# Sensor-platiene.net
KiCad netlist of a schematic drawn in EAGLE
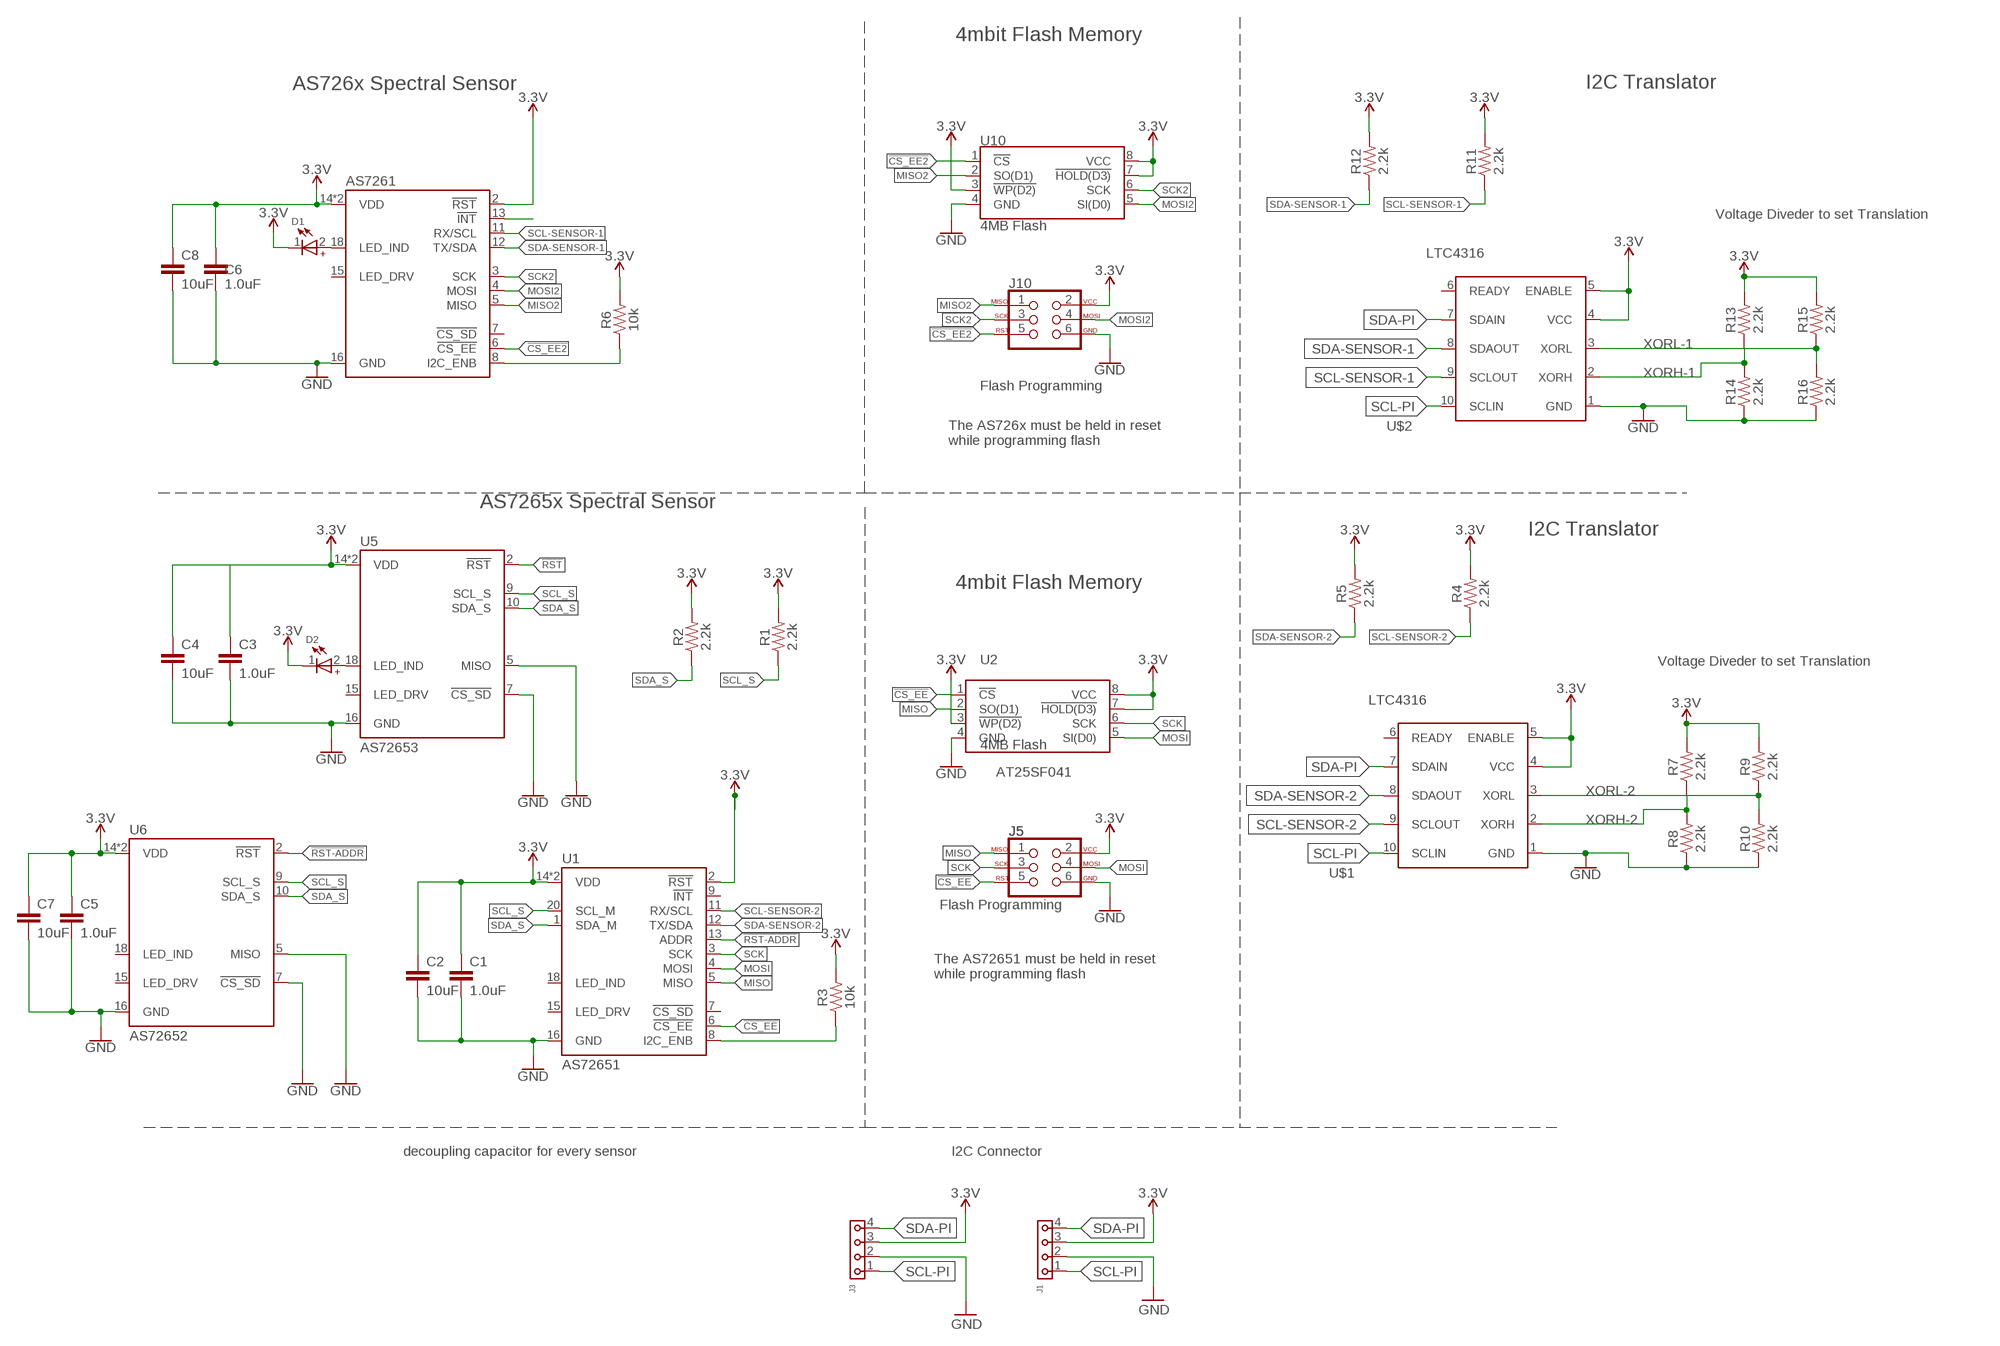
[diagram p0: schematic, sheet 1]

(export (version "E")
  (design (tool "Eeschema 10.0.6"))
  (components
    (comp (ref "AS7261")
      (value "IR")
      (footprint "eagle-import:LGA20")
      (libsource (lib "eagle-import") (part "AS726XIR"))
    )
    (comp (ref "C1")
      (value "1.0uF")
      (footprint "eagle-import:0603")
      (libsource (lib "eagle-import") (part "1.0UF-0603-16V-10%"))
    )
    (comp (ref "C2")
      (value "10uF")
      (footprint "eagle-import:0603")
      (libsource (lib "eagle-import") (part "10UF-0603-6.3V-20%"))
    )
    (comp (ref "C3")
      (value "1.0uF")
      (footprint "eagle-import:0603")
      (libsource (lib "eagle-import") (part "1.0UF-0603-16V-10%"))
    )
    (comp (ref "C4")
      (value "10uF")
      (footprint "eagle-import:0603")
      (libsource (lib "eagle-import") (part "10UF-0603-6.3V-20%"))
    )
    (comp (ref "C5")
      (value "1.0uF")
      (footprint "eagle-import:0603")
      (libsource (lib "eagle-import") (part "1.0UF-0603-16V-10%"))
    )
    (comp (ref "C6")
      (value "1.0uF")
      (footprint "eagle-import:0603")
      (libsource (lib "eagle-import") (part "1.0UF-0603-16V-10%"))
    )
    (comp (ref "C7")
      (value "10uF")
      (footprint "eagle-import:0603")
      (libsource (lib "eagle-import") (part "10UF-0603-6.3V-20%"))
    )
    (comp (ref "C8")
      (value "10uF")
      (footprint "eagle-import:0603")
      (libsource (lib "eagle-import") (part "10UF-0603-6.3V-20%"))
    )
    (comp (ref "D1")
      (value "WL-SMCW_1206_150120RS75000")
      (footprint "eagle-import:WL-SMCW_1206")
      (libsource (lib "eagle-import") (part "WL-SMCW_1206_150120RS75000"))
    )
    (comp (ref "D2")
      (value "WL-SMCW_1206_150120RS75000")
      (footprint "eagle-import:WL-SMCW_1206")
      (libsource (lib "eagle-import") (part "WL-SMCW_1206_150120RS75000"))
    )
    (comp (ref "J1")
      (value "6130XX11821_61300411821")
      (footprint "eagle-import:61300411821")
      (libsource (lib "eagle-import") (part "6130XX11821_61300411821"))
    )
    (comp (ref "J3")
      (value "6130XX11821_61300411821")
      (footprint "eagle-import:61300411821")
      (libsource (lib "eagle-import") (part "6130XX11821_61300411821"))
    )
    (comp (ref "J5")
      (value "Flash Programming")
      (footprint "eagle-import:2X3_TEST_POINTS")
      (libsource (lib "eagle-import") (part "AVR_SPI_PROG_3X2TESTPOINTS"))
    )
    (comp (ref "J10")
      (value "Flash Programming")
      (footprint "eagle-import:2X3_TEST_POINTS")
      (libsource (lib "eagle-import") (part "AVR_SPI_PROG_3X2TESTPOINTS"))
    )
    (comp (ref "R1")
      (value "2.2k")
      (footprint "eagle-import:0603")
      (libsource (lib "eagle-import") (part "2.2KOHM-0603-1/10W-1%"))
    )
    (comp (ref "R2")
      (value "2.2k")
      (footprint "eagle-import:0603")
      (libsource (lib "eagle-import") (part "2.2KOHM-0603-1/10W-1%"))
    )
    (comp (ref "R3")
      (value "10k")
      (footprint "eagle-import:0603")
      (libsource (lib "eagle-import") (part "10KOHM-0603-1/10W-1%"))
    )
    (comp (ref "R4")
      (value "2.2k")
      (footprint "eagle-import:0603")
      (libsource (lib "eagle-import") (part "2.2KOHM-0603-1/10W-1%"))
    )
    (comp (ref "R5")
      (value "2.2k")
      (footprint "eagle-import:0603")
      (libsource (lib "eagle-import") (part "2.2KOHM-0603-1/10W-1%"))
    )
    (comp (ref "R6")
      (value "10k")
      (footprint "eagle-import:0603")
      (libsource (lib "eagle-import") (part "10KOHM-0603-1/10W-1%"))
    )
    (comp (ref "R7")
      (value "2.2k")
      (footprint "eagle-import:0603")
      (libsource (lib "eagle-import") (part "2.2KOHM-0603-1/10W-1%"))
    )
    (comp (ref "R8")
      (value "2.2k")
      (footprint "eagle-import:0603")
      (libsource (lib "eagle-import") (part "2.2KOHM-0603-1/10W-1%"))
    )
    (comp (ref "R9")
      (value "2.2k")
      (footprint "eagle-import:0603")
      (libsource (lib "eagle-import") (part "2.2KOHM-0603-1/10W-1%"))
    )
    (comp (ref "R10")
      (value "2.2k")
      (footprint "eagle-import:0603")
      (libsource (lib "eagle-import") (part "2.2KOHM-0603-1/10W-1%"))
    )
    (comp (ref "R11")
      (value "2.2k")
      (footprint "eagle-import:0603")
      (libsource (lib "eagle-import") (part "2.2KOHM-0603-1/10W-1%"))
    )
    (comp (ref "R12")
      (value "2.2k")
      (footprint "eagle-import:0603")
      (libsource (lib "eagle-import") (part "2.2KOHM-0603-1/10W-1%"))
    )
    (comp (ref "R13")
      (value "2.2k")
      (footprint "eagle-import:0603")
      (libsource (lib "eagle-import") (part "2.2KOHM-0603-1/10W-1%"))
    )
    (comp (ref "R14")
      (value "2.2k")
      (footprint "eagle-import:0603")
      (libsource (lib "eagle-import") (part "2.2KOHM-0603-1/10W-1%"))
    )
    (comp (ref "R15")
      (value "2.2k")
      (footprint "eagle-import:0603")
      (libsource (lib "eagle-import") (part "2.2KOHM-0603-1/10W-1%"))
    )
    (comp (ref "R16")
      (value "2.2k")
      (footprint "eagle-import:0603")
      (libsource (lib "eagle-import") (part "2.2KOHM-0603-1/10W-1%"))
    )
    (comp (ref "U$1")
      (value "LTC4316")
      (footprint "eagle-import:MS-PACKAGE")
      (libsource (lib "eagle-import") (part "LTC4316"))
    )
    (comp (ref "U$2")
      (value "LTC4316")
      (footprint "eagle-import:MS-PACKAGE")
      (libsource (lib "eagle-import") (part "LTC4316"))
    )
    (comp (ref "U1")
      (value "AS72651")
      (footprint "eagle-import:LGA20")
      (libsource (lib "eagle-import") (part "AS72651"))
    )
    (comp (ref "U2")
      (value "4MB Flash")
      (footprint "eagle-import:SO08")
      (libsource (lib "eagle-import") (part "AT25SF041"))
    )
    (comp (ref "U5")
      (value "AS72653")
      (footprint "eagle-import:LGA20")
      (libsource (lib "eagle-import") (part "AS72653"))
    )
    (comp (ref "U6")
      (value "AS72652")
      (footprint "eagle-import:LGA20")
      (libsource (lib "eagle-import") (part "AS72652"))
    )
    (comp (ref "U10")
      (value "4MB Flash")
      (footprint "eagle-import:SO08")
      (libsource (lib "eagle-import") (part "AT25SF041"))
    )
  )
  (nets
    (net (code "1") (name "/XORH-1") (class "Default")
      (node (ref "R13") (pin "1") (pinfunction "1_1") (pintype "passive"))
      (node (ref "R14") (pin "2") (pinfunction "2_2") (pintype "passive"))
      (node (ref "U$2") (pin "2") (pinfunction "XORH_2") (pintype "bidirectional"))
    )
    (net (code "2") (name "/XORH-2") (class "Default")
      (node (ref "R7") (pin "1") (pinfunction "1_1") (pintype "passive"))
      (node (ref "R8") (pin "2") (pinfunction "2_2") (pintype "passive"))
      (node (ref "U$1") (pin "2") (pinfunction "XORH_2") (pintype "bidirectional"))
    )
    (net (code "3") (name "/XORL-1") (class "Default")
      (node (ref "R15") (pin "1") (pinfunction "1_1") (pintype "passive"))
      (node (ref "R16") (pin "2") (pinfunction "2_2") (pintype "passive"))
      (node (ref "U$2") (pin "3") (pinfunction "XORL_3") (pintype "bidirectional"))
    )
    (net (code "4") (name "/XORL-2") (class "Default")
      (node (ref "R10") (pin "2") (pinfunction "2_2") (pintype "passive"))
      (node (ref "R9") (pin "1") (pinfunction "1_1") (pintype "passive"))
      (node (ref "U$1") (pin "3") (pinfunction "XORL_3") (pintype "bidirectional"))
    )
    (net (code "5") (name "/~{CS_EE2}") (class "Default")
      (node (ref "AS7261") (pin "6") (pinfunction "~{CS_EE}_6") (pintype "bidirectional"))
      (node (ref "J10") (pin "5") (pinfunction "5_5") (pintype "passive"))
      (node (ref "U10") (pin "1") (pinfunction "~{CS}_1") (pintype "bidirectional"))
    )
    (net (code "6") (name "/~{CS_EE}") (class "Default")
      (node (ref "J5") (pin "5") (pinfunction "5_5") (pintype "passive"))
      (node (ref "U1") (pin "6") (pinfunction "~{CS_EE}_6") (pintype "bidirectional"))
      (node (ref "U2") (pin "1") (pinfunction "~{CS}_1") (pintype "bidirectional"))
    )
    (net (code "7") (name "/~{RST-ADDR}") (class "Default")
      (node (ref "U1") (pin "13") (pinfunction "ADDR_13") (pintype "bidirectional"))
      (node (ref "U6") (pin "2") (pinfunction "~{RST}_2") (pintype "bidirectional"))
    )
    (net (code "8") (name "/~{RST}") (class "Default")
      (node (ref "U5") (pin "2") (pinfunction "~{RST}_2") (pintype "bidirectional"))
    )
    (net (code "9") (name "3.3V") (class "Default")
      (node (ref "AS7261") (pin "14") (pinfunction "VDD_14") (pintype "bidirectional"))
      (node (ref "AS7261") (pin "17") (pinfunction "VDD_17") (pintype "bidirectional"))
      (node (ref "AS7261") (pin "2") (pinfunction "~{RST}_2") (pintype "bidirectional"))
      (node (ref "C1") (pin "1") (pinfunction "1_1") (pintype "passive"))
      (node (ref "C2") (pin "1") (pinfunction "1_1") (pintype "passive"))
      (node (ref "C3") (pin "1") (pinfunction "1_1") (pintype "passive"))
      (node (ref "C4") (pin "1") (pinfunction "1_1") (pintype "passive"))
      (node (ref "C5") (pin "1") (pinfunction "1_1") (pintype "passive"))
      (node (ref "C6") (pin "1") (pinfunction "1_1") (pintype "passive"))
      (node (ref "C7") (pin "1") (pinfunction "1_1") (pintype "passive"))
      (node (ref "C8") (pin "1") (pinfunction "1_1") (pintype "passive"))
      (node (ref "D1") (pin "1") (pinfunction "-_1") (pintype "passive"))
      (node (ref "D2") (pin "1") (pinfunction "-_1") (pintype "passive"))
      (node (ref "J1") (pin "3") (pinfunction "3_3") (pintype "passive"))
      (node (ref "J10") (pin "2") (pinfunction "2_2") (pintype "passive"))
      (node (ref "J3") (pin "3") (pinfunction "3_3") (pintype "passive"))
      (node (ref "J5") (pin "2") (pinfunction "2_2") (pintype "passive"))
      (node (ref "R1") (pin "2") (pinfunction "2_2") (pintype "passive"))
      (node (ref "R11") (pin "2") (pinfunction "2_2") (pintype "passive"))
      (node (ref "R12") (pin "2") (pinfunction "2_2") (pintype "passive"))
      (node (ref "R13") (pin "2") (pinfunction "2_2") (pintype "passive"))
      (node (ref "R15") (pin "2") (pinfunction "2_2") (pintype "passive"))
      (node (ref "R2") (pin "2") (pinfunction "2_2") (pintype "passive"))
      (node (ref "R3") (pin "2") (pinfunction "2_2") (pintype "passive"))
      (node (ref "R4") (pin "2") (pinfunction "2_2") (pintype "passive"))
      (node (ref "R5") (pin "2") (pinfunction "2_2") (pintype "passive"))
      (node (ref "R6") (pin "2") (pinfunction "2_2") (pintype "passive"))
      (node (ref "R7") (pin "2") (pinfunction "2_2") (pintype "passive"))
      (node (ref "R9") (pin "2") (pinfunction "2_2") (pintype "passive"))
      (node (ref "U$1") (pin "4") (pinfunction "VCC_4") (pintype "bidirectional"))
      (node (ref "U$1") (pin "5") (pinfunction "ENABLE_5") (pintype "bidirectional"))
      (node (ref "U$2") (pin "4") (pinfunction "VCC_4") (pintype "bidirectional"))
      (node (ref "U$2") (pin "5") (pinfunction "ENABLE_5") (pintype "bidirectional"))
      (node (ref "U1") (pin "14") (pinfunction "VDD_14") (pintype "bidirectional"))
      (node (ref "U1") (pin "17") (pinfunction "VDD_17") (pintype "bidirectional"))
      (node (ref "U1") (pin "2") (pinfunction "~{RST}_2") (pintype "bidirectional"))
      (node (ref "U10") (pin "3") (pinfunction "~{WP(D2})_3") (pintype "bidirectional"))
      (node (ref "U10") (pin "7") (pinfunction "~{HOLD(D3})_7") (pintype "bidirectional"))
      (node (ref "U10") (pin "8") (pinfunction "VCC_8") (pintype "bidirectional"))
      (node (ref "U2") (pin "3") (pinfunction "~{WP(D2})_3") (pintype "bidirectional"))
      (node (ref "U2") (pin "7") (pinfunction "~{HOLD(D3})_7") (pintype "bidirectional"))
      (node (ref "U2") (pin "8") (pinfunction "VCC_8") (pintype "bidirectional"))
      (node (ref "U5") (pin "14") (pinfunction "VDD_14") (pintype "bidirectional"))
      (node (ref "U5") (pin "17") (pinfunction "VDD_17") (pintype "bidirectional"))
      (node (ref "U6") (pin "14") (pinfunction "VDD_14") (pintype "bidirectional"))
      (node (ref "U6") (pin "17") (pinfunction "VDD_17") (pintype "bidirectional"))
    )
    (net (code "10") (name "GND") (class "Default")
      (node (ref "AS7261") (pin "16") (pinfunction "GND_16") (pintype "bidirectional"))
      (node (ref "C1") (pin "2") (pinfunction "2_2") (pintype "passive"))
      (node (ref "C2") (pin "2") (pinfunction "2_2") (pintype "passive"))
      (node (ref "C3") (pin "2") (pinfunction "2_2") (pintype "passive"))
      (node (ref "C4") (pin "2") (pinfunction "2_2") (pintype "passive"))
      (node (ref "C5") (pin "2") (pinfunction "2_2") (pintype "passive"))
      (node (ref "C6") (pin "2") (pinfunction "2_2") (pintype "passive"))
      (node (ref "C7") (pin "2") (pinfunction "2_2") (pintype "passive"))
      (node (ref "C8") (pin "2") (pinfunction "2_2") (pintype "passive"))
      (node (ref "J1") (pin "2") (pinfunction "2_2") (pintype "passive"))
      (node (ref "J10") (pin "6") (pinfunction "6_6") (pintype "passive"))
      (node (ref "J3") (pin "2") (pinfunction "2_2") (pintype "passive"))
      (node (ref "J5") (pin "6") (pinfunction "6_6") (pintype "passive"))
      (node (ref "R10") (pin "1") (pinfunction "1_1") (pintype "passive"))
      (node (ref "R14") (pin "1") (pinfunction "1_1") (pintype "passive"))
      (node (ref "R16") (pin "1") (pinfunction "1_1") (pintype "passive"))
      (node (ref "R8") (pin "1") (pinfunction "1_1") (pintype "passive"))
      (node (ref "U$1") (pin "1") (pinfunction "GND_1") (pintype "bidirectional"))
      (node (ref "U$2") (pin "1") (pinfunction "GND_1") (pintype "bidirectional"))
      (node (ref "U1") (pin "16") (pinfunction "GND_16") (pintype "bidirectional"))
      (node (ref "U10") (pin "4") (pinfunction "GND_4") (pintype "bidirectional"))
      (node (ref "U2") (pin "4") (pinfunction "GND_4") (pintype "bidirectional"))
      (node (ref "U5") (pin "16") (pinfunction "GND_16") (pintype "bidirectional"))
      (node (ref "U5") (pin "5") (pinfunction "MISO_5") (pintype "bidirectional"))
      (node (ref "U5") (pin "7") (pinfunction "~{CS_SD}_7") (pintype "bidirectional"))
      (node (ref "U6") (pin "16") (pinfunction "GND_16") (pintype "bidirectional"))
      (node (ref "U6") (pin "5") (pinfunction "MISO_5") (pintype "bidirectional"))
      (node (ref "U6") (pin "7") (pinfunction "~{CS_SD}_7") (pintype "bidirectional"))
    )
    (net (code "11") (name "MISO") (class "Default")
      (node (ref "J5") (pin "1") (pinfunction "1_1") (pintype "passive"))
      (node (ref "U1") (pin "5") (pinfunction "MISO_5") (pintype "bidirectional"))
      (node (ref "U2") (pin "2") (pinfunction "SO(D1)_2") (pintype "bidirectional"))
    )
    (net (code "12") (name "MISO2") (class "Default")
      (node (ref "AS7261") (pin "5") (pinfunction "MISO_5") (pintype "bidirectional"))
      (node (ref "J10") (pin "1") (pinfunction "1_1") (pintype "passive"))
      (node (ref "U10") (pin "2") (pinfunction "SO(D1)_2") (pintype "bidirectional"))
    )
    (net (code "13") (name "MOSI") (class "Default")
      (node (ref "J5") (pin "4") (pinfunction "4_4") (pintype "passive"))
      (node (ref "U1") (pin "4") (pinfunction "MOSI_4") (pintype "bidirectional"))
      (node (ref "U2") (pin "5") (pinfunction "SI(D0)_5") (pintype "bidirectional"))
    )
    (net (code "14") (name "MOSI2") (class "Default")
      (node (ref "AS7261") (pin "4") (pinfunction "MOSI_4") (pintype "bidirectional"))
      (node (ref "J10") (pin "4") (pinfunction "4_4") (pintype "passive"))
      (node (ref "U10") (pin "5") (pinfunction "SI(D0)_5") (pintype "bidirectional"))
    )
    (net (code "15") (name "Net-(AS7261-I2C_ENB)") (class "Default")
      (node (ref "AS7261") (pin "8") (pinfunction "I2C_ENB_8") (pintype "bidirectional"))
      (node (ref "R6") (pin "1") (pinfunction "1_1") (pintype "passive"))
    )
    (net (code "16") (name "Net-(AS7261-LED_IND)") (class "Default")
      (node (ref "AS7261") (pin "18") (pinfunction "LED_IND_18") (pintype "bidirectional"))
      (node (ref "D1") (pin "2") (pinfunction "+_2") (pintype "passive"))
    )
    (net (code "17") (name "Net-(D2-+)") (class "Default")
      (node (ref "D2") (pin "2") (pinfunction "+_2") (pintype "passive"))
      (node (ref "U5") (pin "18") (pinfunction "LED_IND_18") (pintype "bidirectional"))
    )
    (net (code "18") (name "Net-(U1-I2C_ENB)") (class "Default")
      (node (ref "R3") (pin "1") (pinfunction "1_1") (pintype "passive"))
      (node (ref "U1") (pin "8") (pinfunction "I2C_ENB_8") (pintype "bidirectional"))
    )
    (net (code "19") (name "SCK") (class "Default")
      (node (ref "J5") (pin "3") (pinfunction "3_3") (pintype "passive"))
      (node (ref "U1") (pin "3") (pinfunction "SCK_3") (pintype "bidirectional"))
      (node (ref "U2") (pin "6") (pinfunction "SCK_6") (pintype "bidirectional"))
    )
    (net (code "20") (name "SCK2") (class "Default")
      (node (ref "AS7261") (pin "3") (pinfunction "SCK_3") (pintype "bidirectional"))
      (node (ref "J10") (pin "3") (pinfunction "3_3") (pintype "passive"))
      (node (ref "U10") (pin "6") (pinfunction "SCK_6") (pintype "bidirectional"))
    )
    (net (code "21") (name "SCL-PI") (class "Default")
      (node (ref "J1") (pin "1") (pinfunction "1_1") (pintype "passive"))
      (node (ref "J3") (pin "1") (pinfunction "1_1") (pintype "passive"))
      (node (ref "U$1") (pin "10") (pinfunction "SCLIN_10") (pintype "bidirectional"))
      (node (ref "U$2") (pin "10") (pinfunction "SCLIN_10") (pintype "bidirectional"))
    )
    (net (code "22") (name "SCL-SENSOR-1") (class "Default")
      (node (ref "AS7261") (pin "11") (pinfunction "RX/SCL_11") (pintype "bidirectional"))
      (node (ref "R11") (pin "1") (pinfunction "1_1") (pintype "passive"))
      (node (ref "U$2") (pin "9") (pinfunction "SCLOUT_9") (pintype "bidirectional"))
    )
    (net (code "23") (name "SCL-SENSOR-2") (class "Default")
      (node (ref "R4") (pin "1") (pinfunction "1_1") (pintype "passive"))
      (node (ref "U$1") (pin "9") (pinfunction "SCLOUT_9") (pintype "bidirectional"))
      (node (ref "U1") (pin "11") (pinfunction "RX/SCL_11") (pintype "bidirectional"))
    )
    (net (code "24") (name "SCL_S") (class "Default")
      (node (ref "R1") (pin "1") (pinfunction "1_1") (pintype "passive"))
      (node (ref "U1") (pin "20") (pinfunction "SCL_M_20") (pintype "bidirectional"))
      (node (ref "U5") (pin "9") (pinfunction "SCL_S_9") (pintype "bidirectional"))
      (node (ref "U6") (pin "9") (pinfunction "SCL_S_9") (pintype "bidirectional"))
    )
    (net (code "25") (name "SDA-PI") (class "Default")
      (node (ref "J1") (pin "4") (pinfunction "4_4") (pintype "passive"))
      (node (ref "J3") (pin "4") (pinfunction "4_4") (pintype "passive"))
      (node (ref "U$1") (pin "7") (pinfunction "SDAIN_7") (pintype "bidirectional"))
      (node (ref "U$2") (pin "7") (pinfunction "SDAIN_7") (pintype "bidirectional"))
    )
    (net (code "26") (name "SDA-SENSOR-1") (class "Default")
      (node (ref "AS7261") (pin "12") (pinfunction "TX/SDA_12") (pintype "bidirectional"))
      (node (ref "R12") (pin "1") (pinfunction "1_1") (pintype "passive"))
      (node (ref "U$2") (pin "8") (pinfunction "SDAOUT_8") (pintype "bidirectional"))
    )
    (net (code "27") (name "SDA-SENSOR-2") (class "Default")
      (node (ref "R5") (pin "1") (pinfunction "1_1") (pintype "passive"))
      (node (ref "U$1") (pin "8") (pinfunction "SDAOUT_8") (pintype "bidirectional"))
      (node (ref "U1") (pin "12") (pinfunction "TX/SDA_12") (pintype "bidirectional"))
    )
    (net (code "28") (name "SDA_S") (class "Default")
      (node (ref "R2") (pin "1") (pinfunction "1_1") (pintype "passive"))
      (node (ref "U1") (pin "1") (pinfunction "SDA_M_1") (pintype "bidirectional"))
      (node (ref "U5") (pin "10") (pinfunction "SDA_S_10") (pintype "bidirectional"))
      (node (ref "U6") (pin "10") (pinfunction "SDA_S_10") (pintype "bidirectional"))
    )
    (net (code "29") (name "unconnected-(AS7261-LED_DRV-Pad15)") (class "Default")
      (node (ref "AS7261") (pin "15") (pinfunction "LED_DRV_15") (pintype "bidirectional"))
    )
    (net (code "30") (name "unconnected-(AS7261-~{CS_SD}-Pad7)") (class "Default")
      (node (ref "AS7261") (pin "7") (pinfunction "~{CS_SD}_7") (pintype "bidirectional"))
    )
    (net (code "31") (name "unconnected-(AS7261-~{INT}-Pad13)") (class "Default")
      (node (ref "AS7261") (pin "13") (pinfunction "~{INT}_13") (pintype "bidirectional"))
    )
    (net (code "32") (name "unconnected-(U$1-READY-Pad6)") (class "Default")
      (node (ref "U$1") (pin "6") (pinfunction "READY_6") (pintype "bidirectional"))
    )
    (net (code "33") (name "unconnected-(U$2-READY-Pad6)") (class "Default")
      (node (ref "U$2") (pin "6") (pinfunction "READY_6") (pintype "bidirectional"))
    )
    (net (code "34") (name "unconnected-(U1-LED_DRV-Pad15)") (class "Default")
      (node (ref "U1") (pin "15") (pinfunction "LED_DRV_15") (pintype "bidirectional"))
    )
    (net (code "35") (name "unconnected-(U1-LED_IND-Pad18)") (class "Default")
      (node (ref "U1") (pin "18") (pinfunction "LED_IND_18") (pintype "bidirectional"))
    )
    (net (code "36") (name "unconnected-(U1-~{CS_SD}-Pad7)") (class "Default")
      (node (ref "U1") (pin "7") (pinfunction "~{CS_SD}_7") (pintype "bidirectional"))
    )
    (net (code "37") (name "unconnected-(U1-~{INT}-Pad9)") (class "Default")
      (node (ref "U1") (pin "9") (pinfunction "~{INT}_9") (pintype "bidirectional"))
    )
    (net (code "38") (name "unconnected-(U5-LED_DRV-Pad15)") (class "Default")
      (node (ref "U5") (pin "15") (pinfunction "LED_DRV_15") (pintype "bidirectional"))
    )
    (net (code "39") (name "unconnected-(U6-LED_DRV-Pad15)") (class "Default")
      (node (ref "U6") (pin "15") (pinfunction "LED_DRV_15") (pintype "bidirectional"))
    )
    (net (code "40") (name "unconnected-(U6-LED_IND-Pad18)") (class "Default")
      (node (ref "U6") (pin "18") (pinfunction "LED_IND_18") (pintype "bidirectional"))
    )
  )
)
